# Schematc_automa_contatore.net
KiCad netlist of a schematic drawn in EAGLE
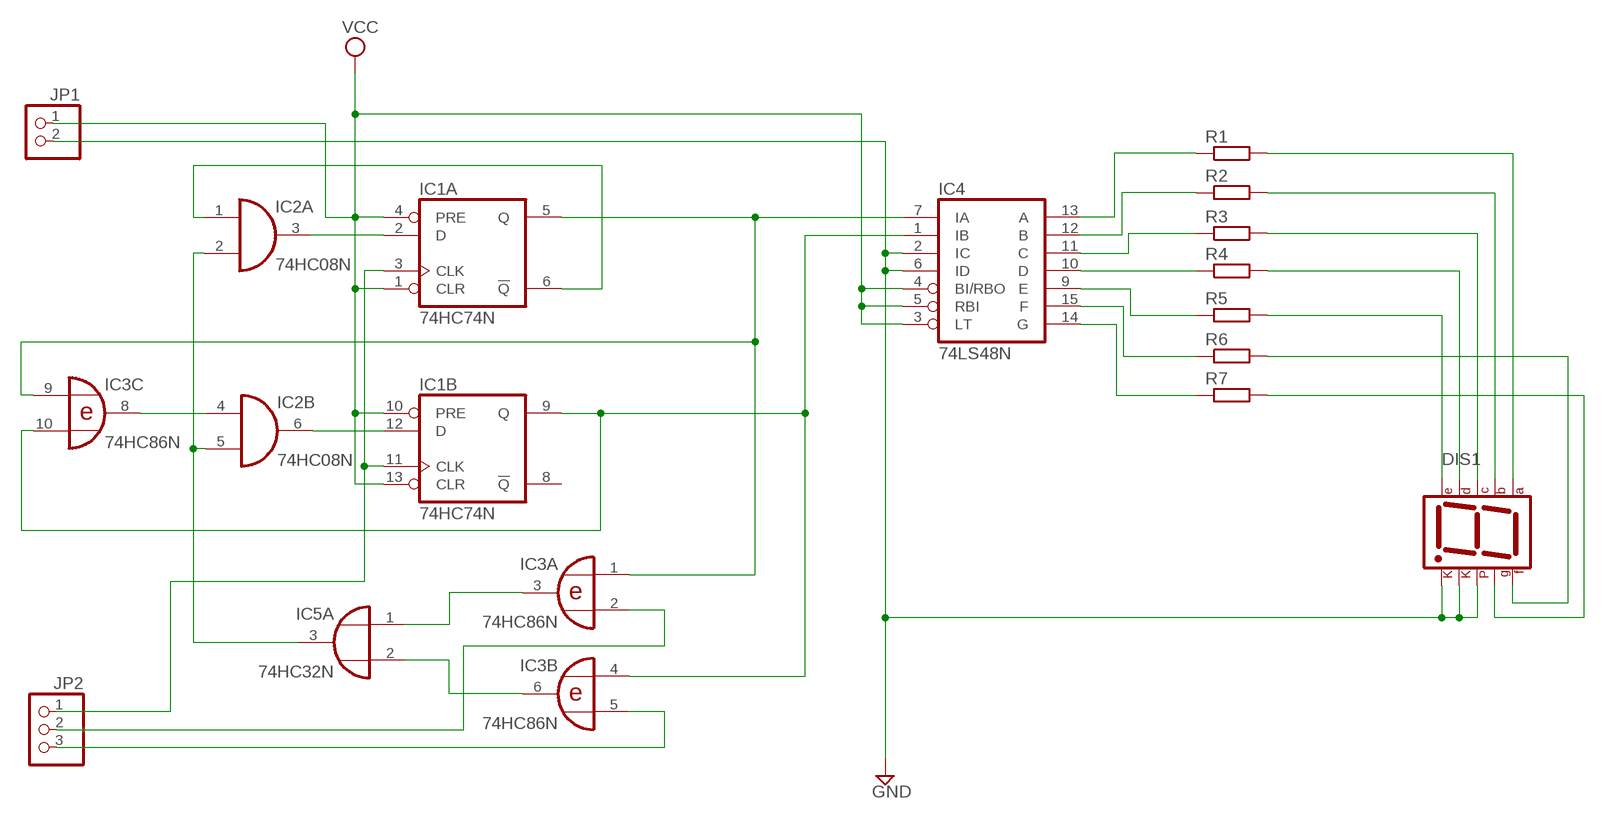
[diagram p0: schematic, sheet 1]

(export (version "E")
  (design (tool "Eeschema 10.0.6"))
  (components
    (comp (ref "DIS1")
      (value "7SEG-CK")
      (footprint "eagle-import:7SEG-13")
      (libsource (lib "eagle-import") (part "7SEG-CK"))
    )
    (comp (ref "IC1")
      (value "74HC74N")
      (footprint "eagle-import:DIL14")
      (libsource (lib "eagle-import") (part "7474NHC"))
    )
    (comp (ref "IC2")
      (value "74HC08N")
      (footprint "eagle-import:DIL14")
      (libsource (lib "eagle-import") (part "7408NHC"))
    )
    (comp (ref "IC3")
      (value "74HC86N")
      (footprint "eagle-import:DIL14")
      (libsource (lib "eagle-import") (part "7486NHC"))
    )
    (comp (ref "IC4")
      (value "74LS48N")
      (footprint "eagle-import:DIL16")
      (libsource (lib "eagle-import") (part "7448NLS"))
    )
    (comp (ref "IC5")
      (value "74HC32N")
      (footprint "eagle-import:DIL14")
      (libsource (lib "eagle-import") (part "7432NHC"))
    )
    (comp (ref "JP1")
      (value "PINHD-1X2")
      (footprint "eagle-import:1X02")
      (libsource (lib "eagle-import") (part "PINHD-1X2"))
    )
    (comp (ref "JP2")
      (value "PINHD-1X3")
      (footprint "eagle-import:1X03")
      (libsource (lib "eagle-import") (part "PINHD-1X3"))
    )
    (comp (ref "R1")
      (value "R-EU_0204/5")
      (footprint "eagle-import:0204_5")
      (libsource (lib "eagle-import") (part "R-EU_0204/5"))
    )
    (comp (ref "R2")
      (value "R-EU_0204/5")
      (footprint "eagle-import:0204_5")
      (libsource (lib "eagle-import") (part "R-EU_0204/5"))
    )
    (comp (ref "R3")
      (value "R-EU_0204/5")
      (footprint "eagle-import:0204_5")
      (libsource (lib "eagle-import") (part "R-EU_0204/5"))
    )
    (comp (ref "R4")
      (value "R-EU_0204/5")
      (footprint "eagle-import:0204_5")
      (libsource (lib "eagle-import") (part "R-EU_0204/5"))
    )
    (comp (ref "R5")
      (value "R-EU_0204/5")
      (footprint "eagle-import:0204_5")
      (libsource (lib "eagle-import") (part "R-EU_0204/5"))
    )
    (comp (ref "R6")
      (value "R-EU_0204/5")
      (footprint "eagle-import:0204_5")
      (libsource (lib "eagle-import") (part "R-EU_0204/5"))
    )
    (comp (ref "R7")
      (value "R-EU_0204/5")
      (footprint "eagle-import:0204_5")
      (libsource (lib "eagle-import") (part "R-EU_0204/5"))
    )
  )
  (nets
    (net (code "1") (name "GND") (class "Default")
      (node (ref "DIS1") (pin "3") (pinfunction "CK1_3") (pintype "passive"))
      (node (ref "DIS1") (pin "5") (pinfunction "DP_5") (pintype "passive"))
      (node (ref "DIS1") (pin "8") (pinfunction "CK2_8") (pintype "passive"))
      (node (ref "IC4") (pin "2") (pinfunction "IC_2") (pintype "input"))
      (node (ref "IC4") (pin "6") (pinfunction "ID_6") (pintype "input"))
      (node (ref "JP1") (pin "2") (pinfunction "2_2") (pintype "passive"))
    )
    (net (code "2") (name "Net-(DIS1-A)") (class "Default")
      (node (ref "DIS1") (pin "7") (pinfunction "A_7") (pintype "passive"))
      (node (ref "R1") (pin "2") (pinfunction "2_2") (pintype "passive"))
    )
    (net (code "3") (name "Net-(DIS1-B)") (class "Default")
      (node (ref "DIS1") (pin "6") (pinfunction "B_6") (pintype "passive"))
      (node (ref "R2") (pin "2") (pinfunction "2_2") (pintype "passive"))
    )
    (net (code "4") (name "Net-(DIS1-C)") (class "Default")
      (node (ref "DIS1") (pin "4") (pinfunction "C_4") (pintype "passive"))
      (node (ref "R3") (pin "2") (pinfunction "2_2") (pintype "passive"))
    )
    (net (code "5") (name "Net-(DIS1-D)") (class "Default")
      (node (ref "DIS1") (pin "2") (pinfunction "D_2") (pintype "passive"))
      (node (ref "R4") (pin "2") (pinfunction "2_2") (pintype "passive"))
    )
    (net (code "6") (name "Net-(DIS1-E)") (class "Default")
      (node (ref "DIS1") (pin "1") (pinfunction "E_1") (pintype "passive"))
      (node (ref "R5") (pin "2") (pinfunction "2_2") (pintype "passive"))
    )
    (net (code "7") (name "Net-(DIS1-F)") (class "Default")
      (node (ref "DIS1") (pin "9") (pinfunction "F_9") (pintype "passive"))
      (node (ref "R6") (pin "2") (pinfunction "2_2") (pintype "passive"))
    )
    (net (code "8") (name "Net-(DIS1-G)") (class "Default")
      (node (ref "DIS1") (pin "10") (pinfunction "G_10") (pintype "passive"))
      (node (ref "R7") (pin "2") (pinfunction "2_2") (pintype "passive"))
    )
    (net (code "9") (name "Net-(IC1A-CLK)") (class "Default")
      (node (ref "IC1") (pin "11") (pinfunction "CLK_11") (pintype "input"))
      (node (ref "IC1") (pin "3") (pinfunction "CLK_3") (pintype "input"))
      (node (ref "JP2") (pin "1") (pinfunction "1_1") (pintype "passive"))
    )
    (net (code "10") (name "Net-(IC1A-D)") (class "Default")
      (node (ref "IC1") (pin "2") (pinfunction "D_2") (pintype "input"))
      (node (ref "IC2") (pin "3") (pinfunction "O_3") (pintype "output"))
    )
    (net (code "11") (name "Net-(IC1A-Q)") (class "Default")
      (node (ref "IC1") (pin "5") (pinfunction "Q_5") (pintype "output"))
      (node (ref "IC3") (pin "1") (pinfunction "I0_1") (pintype "input"))
      (node (ref "IC3") (pin "9") (pinfunction "I0_9") (pintype "input"))
      (node (ref "IC4") (pin "7") (pinfunction "IA_7") (pintype "input"))
    )
    (net (code "12") (name "Net-(IC1A-~{Q})") (class "Default")
      (node (ref "IC1") (pin "6") (pinfunction "~{Q}_6") (pintype "output"))
      (node (ref "IC2") (pin "1") (pinfunction "I0_1") (pintype "input"))
    )
    (net (code "13") (name "Net-(IC1B-D)") (class "Default")
      (node (ref "IC1") (pin "12") (pinfunction "D_12") (pintype "input"))
      (node (ref "IC2") (pin "6") (pinfunction "O_6") (pintype "output"))
    )
    (net (code "14") (name "Net-(IC1B-Q)") (class "Default")
      (node (ref "IC1") (pin "9") (pinfunction "Q_9") (pintype "output"))
      (node (ref "IC3") (pin "10") (pinfunction "I1_10") (pintype "input"))
      (node (ref "IC3") (pin "4") (pinfunction "I0_4") (pintype "input"))
      (node (ref "IC4") (pin "1") (pinfunction "IB_1") (pintype "input"))
    )
    (net (code "15") (name "Net-(IC2A-I1)") (class "Default")
      (node (ref "IC2") (pin "2") (pinfunction "I1_2") (pintype "input"))
      (node (ref "IC2") (pin "5") (pinfunction "I1_5") (pintype "input"))
      (node (ref "IC5") (pin "3") (pinfunction "O_3") (pintype "output"))
    )
    (net (code "16") (name "Net-(IC2B-I0)") (class "Default")
      (node (ref "IC2") (pin "4") (pinfunction "I0_4") (pintype "input"))
      (node (ref "IC3") (pin "8") (pinfunction "O_8") (pintype "output"))
    )
    (net (code "17") (name "Net-(IC3A-I1)") (class "Default")
      (node (ref "IC3") (pin "2") (pinfunction "I1_2") (pintype "input"))
      (node (ref "JP2") (pin "2") (pinfunction "2_2") (pintype "passive"))
    )
    (net (code "18") (name "Net-(IC3A-O)") (class "Default")
      (node (ref "IC3") (pin "3") (pinfunction "O_3") (pintype "output"))
      (node (ref "IC5") (pin "1") (pinfunction "I0_1") (pintype "input"))
    )
    (net (code "19") (name "Net-(IC3B-I1)") (class "Default")
      (node (ref "IC3") (pin "5") (pinfunction "I1_5") (pintype "input"))
      (node (ref "JP2") (pin "3") (pinfunction "3_3") (pintype "passive"))
    )
    (net (code "20") (name "Net-(IC3B-O)") (class "Default")
      (node (ref "IC3") (pin "6") (pinfunction "O_6") (pintype "output"))
      (node (ref "IC5") (pin "2") (pinfunction "I1_2") (pintype "input"))
    )
    (net (code "21") (name "Net-(IC4A-A)") (class "Default")
      (node (ref "IC4") (pin "13") (pinfunction "A_13") (pintype "output"))
      (node (ref "R1") (pin "1") (pinfunction "1_1") (pintype "passive"))
    )
    (net (code "22") (name "Net-(IC4A-B)") (class "Default")
      (node (ref "IC4") (pin "12") (pinfunction "B_12") (pintype "output"))
      (node (ref "R2") (pin "1") (pinfunction "1_1") (pintype "passive"))
    )
    (net (code "23") (name "Net-(IC4A-C)") (class "Default")
      (node (ref "IC4") (pin "11") (pinfunction "C_11") (pintype "output"))
      (node (ref "R3") (pin "1") (pinfunction "1_1") (pintype "passive"))
    )
    (net (code "24") (name "Net-(IC4A-D)") (class "Default")
      (node (ref "IC4") (pin "10") (pinfunction "D_10") (pintype "output"))
      (node (ref "R4") (pin "1") (pinfunction "1_1") (pintype "passive"))
    )
    (net (code "25") (name "Net-(IC4A-E)") (class "Default")
      (node (ref "IC4") (pin "9") (pinfunction "E_9") (pintype "output"))
      (node (ref "R5") (pin "1") (pinfunction "1_1") (pintype "passive"))
    )
    (net (code "26") (name "Net-(IC4A-F)") (class "Default")
      (node (ref "IC4") (pin "15") (pinfunction "F_15") (pintype "output"))
      (node (ref "R6") (pin "1") (pinfunction "1_1") (pintype "passive"))
    )
    (net (code "27") (name "Net-(IC4A-G)") (class "Default")
      (node (ref "IC4") (pin "14") (pinfunction "G_14") (pintype "output"))
      (node (ref "R7") (pin "1") (pinfunction "1_1") (pintype "passive"))
    )
    (net (code "28") (name "VCC") (class "Default")
      (node (ref "IC1") (pin "1") (pinfunction "CLR_1") (pintype "input"))
      (node (ref "IC1") (pin "10") (pinfunction "PRE_10") (pintype "input"))
      (node (ref "IC1") (pin "13") (pinfunction "CLR_13") (pintype "input"))
      (node (ref "IC1") (pin "4") (pinfunction "PRE_4") (pintype "input"))
      (node (ref "IC4") (pin "3") (pinfunction "LT_3") (pintype "input"))
      (node (ref "IC4") (pin "4") (pinfunction "BI/RBO_4") (pintype "input"))
      (node (ref "IC4") (pin "5") (pinfunction "RBI_5") (pintype "input"))
      (node (ref "JP1") (pin "1") (pinfunction "1_1") (pintype "passive"))
    )
    (net (code "29") (name "unconnected-(IC1B-~{Q}-Pad8)") (class "Default")
      (node (ref "IC1") (pin "8") (pinfunction "~{Q}_8") (pintype "output"))
    )
  )
)
